# zp_zh.net
KiCad netlist of a schematic drawn in Altium Designer
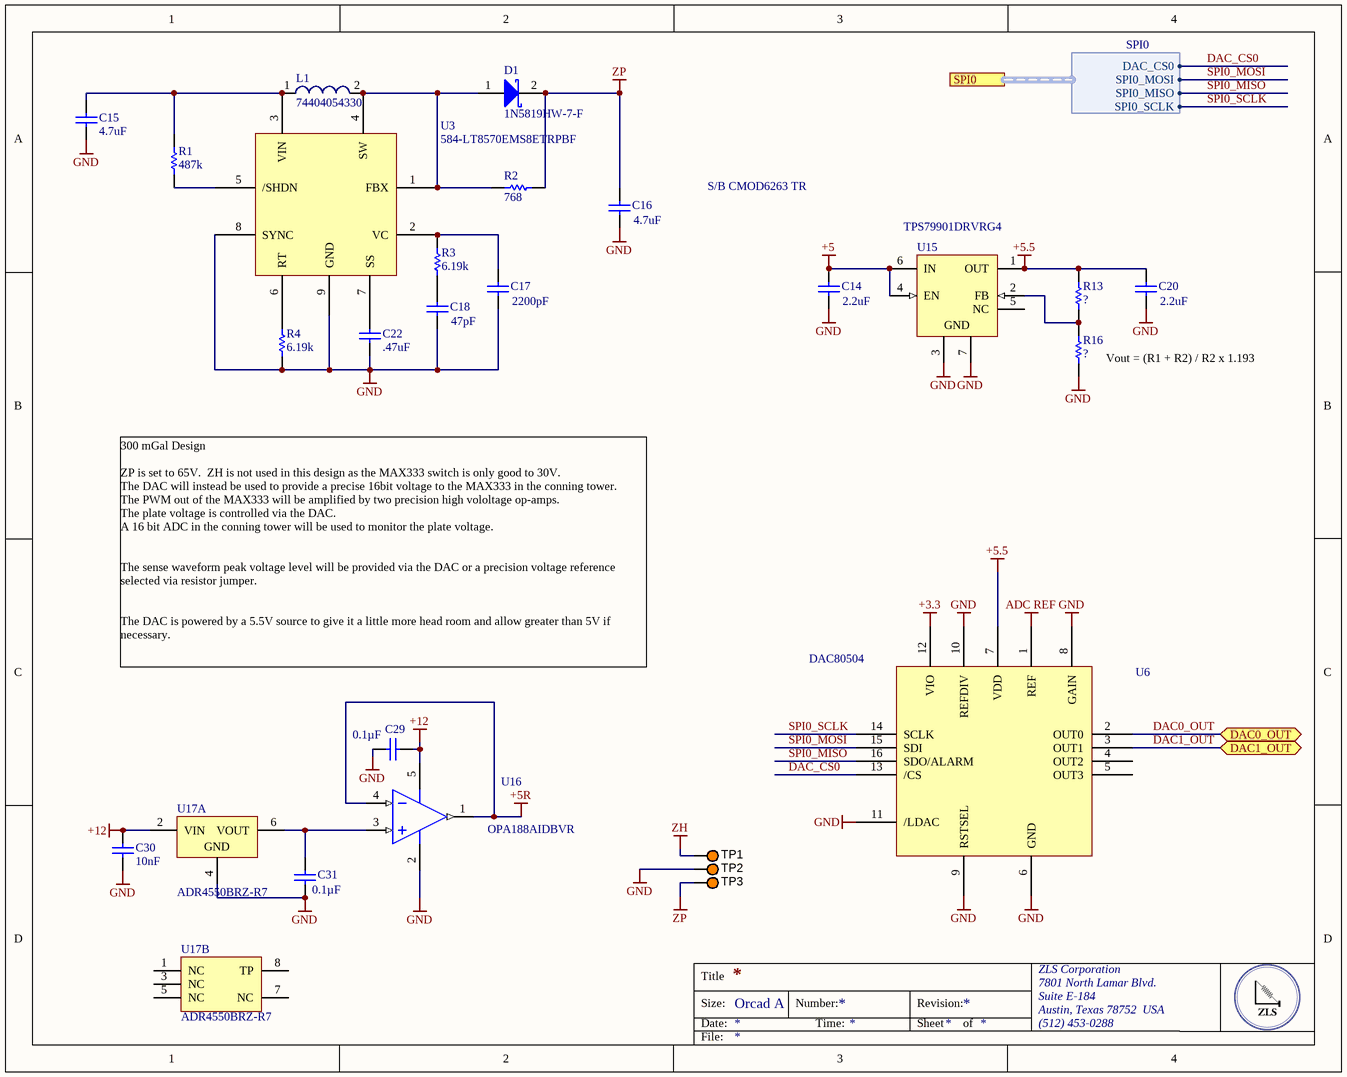
[diagram p0: zp_zh.SchDoc]

(export (version "E")
  (design (tool "Eeschema 10.0.6"))
  (components
    (comp (ref "C14")
      (value "CAP CER 1UF 25V X7R 0805")
      (footprint "CAPC0805(2012)155_L")
      (fields
        (field (name "MANUFACTURER") "Murata Electronics North America")
        (field (name "MANUFACTURER PART NUMBER") "GRM21BR71E105KA99L")
        (field (name "CAPACITANCE") "2.2uF")
        (field (name "TOLERANCE") "±10%")
      )
      (libsource (lib "Altium Content Vault") (part "CMP-1036-04882-1"))
    )
    (comp (ref "C15")
      (value "4.7uF")
      (footprint "CAPC0805(2012)155_L")
      (libsource (lib "Altium Content Vault") (part "CMP-1036-04882-1"))
    )
    (comp (ref "C16")
      (value "CAP CER 1UF 25V X7R 0805")
      (footprint "CAPC0805(2012)155_L")
      (fields
        (field (name "MANUFACTURER") "Murata Electronics North America")
        (field (name "MANUFACTURER PART NUMBER") "GRM21BR71E105KA99L")
        (field (name "CAPACITANCE") "4.7uF")
        (field (name "TOLERANCE") "±10%")
      )
      (libsource (lib "Altium Content Vault") (part "CMP-1036-04882-1"))
    )
    (comp (ref "C17")
      (value "CAP CER 1UF 25V X7R 0805")
      (footprint "CAPC0805(2012)155_L")
      (fields
        (field (name "MANUFACTURER") "Murata Electronics North America")
        (field (name "MANUFACTURER PART NUMBER") "GRM21BR71E105KA99L")
        (field (name "CAPACITANCE") "2200pF")
        (field (name "TOLERANCE") "±10%")
      )
      (libsource (lib "Altium Content Vault") (part "CMP-1036-04882-1"))
    )
    (comp (ref "C18")
      (value "CAP CER 1UF 25V X7R 0805")
      (footprint "CAPC0805(2012)155_L")
      (fields
        (field (name "MANUFACTURER") "Murata Electronics North America")
        (field (name "MANUFACTURER PART NUMBER") "GRM21BR71E105KA99L")
        (field (name "CAPACITANCE") "47pF")
        (field (name "TOLERANCE") "±10%")
      )
      (libsource (lib "Altium Content Vault") (part "CMP-1036-04882-1"))
    )
    (comp (ref "C20")
      (value "CAP CER 1UF 25V X7R 0805")
      (footprint "CAPC0805(2012)155_L")
      (fields
        (field (name "MANUFACTURER") "Murata Electronics North America")
        (field (name "MANUFACTURER PART NUMBER") "GRM21BR71E105KA99L")
        (field (name "CAPACITANCE") "2.2uF")
        (field (name "TOLERANCE") "±10%")
      )
      (libsource (lib "Altium Content Vault") (part "CMP-1036-04882-1"))
    )
    (comp (ref "C22")
      (value ".47uF")
      (footprint "CAPC0805(2012)155_L")
      (libsource (lib "Altium Content Vault") (part "CMP-1036-04882-1"))
    )
    (comp (ref "C29")
      (value "CAP CER 0.1UF 25V X7R 0805")
      (footprint "CAPC0805(2012)145_N")
      (fields
        (field (name "MANUFACTURER") "Murata Electronics North America")
        (field (name "MANUFACTURER PART NUMBER") "GRM21BR71E104KA01L")
        (field (name "CAPACITANCE") "0.1µF")
        (field (name "TOLERANCE") "±10%")
      )
      (libsource (lib "Altium Content Vault") (part "CMP-1036-04795-1"))
    )
    (comp (ref "C30")
      (value "Multilayer Ceramic Capacitors MLCC - SMD/SMT 0.01uF 50volts 10% X7R")
      (footprint "CAPC0805(2012)145_N")
      (fields
        (field (name "MANUFACTURER") "Kemet")
        (field (name "MANUFACTURER PART NUMBER") "C0805C103K5RACAUTO")
        (field (name "CAPACITANCE") "10nF")
        (field (name "TOLERANCE") "10%")
      )
      (libsource (lib "Altium Content Vault") (part "CMP-1036-04795-1"))
    )
    (comp (ref "C31")
      (value "CAP CER 0.1UF 25V X7R 0805")
      (footprint "CAPC0805(2012)145_N")
      (fields
        (field (name "MANUFACTURER") "Murata Electronics North America")
        (field (name "MANUFACTURER PART NUMBER") "GRM21BR71E104KA01L")
        (field (name "CAPACITANCE") "0.1µF")
        (field (name "TOLERANCE") "±10%")
      )
      (libsource (lib "Altium Content Vault") (part "CMP-1036-04795-1"))
    )
    (comp (ref "D1")
      (value "1N5819HW-7-F")
      (footprint "DIOD-SOD-123-2_V")
      (fields (field (name "MANUFACTURER") "Diodes Inc"))
      (libsource (lib "Altium Content Vault") (part "DIOD-DSKY-A1K2-2"))
    )
    (comp (ref "L1")
      (value "74404054330")
      (footprint "WE-LQS 5040")
      (description "WE-LQS SMD Power Inductor, L=33.0 µH")
      (fields (field (name "MANUFACTURER") "Wuerth Elektronik"))
      (libsource (lib "Altium Content Vault") (part "WE-IND-INDUCTOR-2"))
    )
    (comp (ref "R1")
      (value "487k")
      (footprint "RESC0805(2012)_L")
      (libsource (lib "Altium Content Vault") (part "CMP-1013-00215-1"))
    )
    (comp (ref "R2")
      (value "768")
      (footprint "RESC0805(2012)_L")
      (libsource (lib "Altium Content Vault") (part "CMP-1013-00215-1"))
    )
    (comp (ref "R3")
      (value "6.19k")
      (footprint "RESC0805(2012)_L")
      (libsource (lib "Altium Content Vault") (part "CMP-1013-00215-1"))
    )
    (comp (ref "R4")
      (value "6.19k")
      (footprint "RESC0805(2012)_L")
      (libsource (lib "Altium Content Vault") (part "CMP-1013-00215-1"))
    )
    (comp (ref "R13")
      (value "?")
      (footprint "RESC0805(2012)_L")
      (libsource (lib "Altium Content Vault") (part "CMP-1013-00215-1"))
    )
    (comp (ref "R16")
      (value "?")
      (footprint "RESC0805(2012)_L")
      (libsource (lib "Altium Content Vault") (part "CMP-1013-00215-1"))
    )
    (comp (ref "TP1")
      (value "5003")
      (footprint "KSTN-5003")
      (description "Test Point, Orange, 1-Pin THD, RoHS")
      (libsource (lib "Altium Content Vault") (part "CMP-1672-00009-1"))
    )
    (comp (ref "TP2")
      (value "5003")
      (footprint "KSTN-5003")
      (description "Test Point, Orange, 1-Pin THD, RoHS")
      (libsource (lib "Altium Content Vault") (part "CMP-1672-00009-1"))
    )
    (comp (ref "TP3")
      (value "5003")
      (footprint "KSTN-5003")
      (description "Test Point, Orange, 1-Pin THD, RoHS")
      (libsource (lib "Altium Content Vault") (part "CMP-1672-00009-1"))
    )
    (comp (ref "U3")
      (value "LT8570")
      (footprint "LT8570-MSOP")
      (description "IC REG MULT CONFIG INV ADJ 8MSOP")
      (fields (field (name "SUPPLIER PART NUMBER 1") "584-LT8570EMS8ETRPBF"))
      (libsource (lib "ZLS_Schematic_lib") (part "LT8570"))
    )
    (comp (ref "U6")
      (value "DAC80504")
      (footprint "DAC80504")
      (libsource (lib "ZLS_Schematic_lib") (part "DAC80504"))
    )
    (comp (ref "U15")
      (value "TPS79901DRVRG4")
      (footprint "TI-DRV6-1600X1000TP_V")
      (fields (field (name "MANUFACTURER") "Texas Instruments"))
      (libsource (lib "Altium Content Vault") (part "TI-TPS7XXXXDRV6-1600X1000TP"))
    )
    (comp (ref "U16")
      (value "OPA188AIDBVR")
      (footprint "DBV0005A_M")
      (fields (field (name "MANUFACTURER") "Texas Instruments"))
      (libsource (lib "Altium Content Vault") (part "CMP-0809-00005-2"))
    )
    (comp (ref "U17")
      (value "ADR4550BRZ-R7")
      (footprint "ADI-R-8_M")
      (fields (field (name "MANUFACTURER") "Analog Devices"))
      (libsource (lib "Altium Content Vault") (part "ADI-ADR45xx-R-8"))
    )
  )
  (nets
    (net (code "2") (name "+3.3") (class "Default")
      (node (ref "U6") (pin "12") (pinfunction "VIO_12") (pintype "passive"))
    )
    (net (code "3") (name "+5") (class "Default")
      (node (ref "C14") (pin "2") (pinfunction "2_2") (pintype "passive"))
      (node (ref "U15") (pin "4") (pinfunction "EN_4") (pintype "input"))
      (node (ref "U15") (pin "6") (pinfunction "IN_6") (pintype "power_in"))
    )
    (net (code "4") (name "+5.5") (class "Default")
      (node (ref "C20") (pin "2") (pinfunction "2_2") (pintype "passive"))
      (node (ref "R13") (pin "1") (pinfunction "1_1") (pintype "passive"))
      (node (ref "U15") (pin "1") (pinfunction "OUT_1") (pintype "power_in"))
      (node (ref "U6") (pin "7") (pinfunction "VDD_7") (pintype "passive"))
    )
    (net (code "5") (name "+5R") (class "Default")
      (node (ref "U16") (pin "1") (pinfunction "OUT_1") (pintype "output"))
      (node (ref "U16") (pin "4") (pinfunction "IN-_4") (pintype "input"))
    )
    (net (code "6") (name "+12") (class "Default")
      (node (ref "C29") (pin "2") (pinfunction "2_2") (pintype "passive"))
      (node (ref "C30") (pin "1") (pinfunction "1_1") (pintype "passive"))
      (node (ref "U16") (pin "5") (pinfunction "V+_5") (pintype "power_in"))
      (node (ref "U17") (pin "2") (pinfunction "VIN_2") (pintype "power_in"))
    )
    (net (code "7") (name "/DAC0_OUT") (class "Default")
      (node (ref "U6") (pin "2") (pinfunction "OUT0_2") (pintype "passive"))
    )
    (net (code "8") (name "/DAC1_OUT") (class "Default")
      (node (ref "U6") (pin "3") (pinfunction "OUT1_3") (pintype "passive"))
    )
    (net (code "9") (name "/DAC_CS0") (class "Default")
      (node (ref "U6") (pin "13") (pinfunction "/CS_13") (pintype "passive"))
    )
    (net (code "10") (name "/SPI0_MISO") (class "Default")
      (node (ref "U6") (pin "16") (pinfunction "SDO/ALARM_16") (pintype "passive"))
    )
    (net (code "11") (name "/SPI0_MOSI") (class "Default")
      (node (ref "U6") (pin "15") (pinfunction "SDI_15") (pintype "passive"))
    )
    (net (code "12") (name "/SPI0_SCLK") (class "Default")
      (node (ref "U6") (pin "14") (pinfunction "SCLK_14") (pintype "passive"))
    )
    (net (code "14") (name "ADC REF") (class "Default")
      (node (ref "U6") (pin "1") (pinfunction "REF_1") (pintype "passive"))
    )
    (net (code "15") (name "GND") (class "Default")
      (node (ref "C14") (pin "1") (pinfunction "1_1") (pintype "passive"))
      (node (ref "C15") (pin "1") (pinfunction "1_1") (pintype "passive"))
      (node (ref "C16") (pin "1") (pinfunction "1_1") (pintype "passive"))
      (node (ref "C17") (pin "1") (pinfunction "1_1") (pintype "passive"))
      (node (ref "C18") (pin "1") (pinfunction "1_1") (pintype "passive"))
      (node (ref "C20") (pin "1") (pinfunction "1_1") (pintype "passive"))
      (node (ref "C22") (pin "1") (pinfunction "1_1") (pintype "passive"))
      (node (ref "C29") (pin "1") (pinfunction "1_1") (pintype "passive"))
      (node (ref "C30") (pin "2") (pinfunction "2_2") (pintype "passive"))
      (node (ref "C31") (pin "2") (pinfunction "2_2") (pintype "passive"))
      (node (ref "R16") (pin "2") (pinfunction "2_2") (pintype "passive"))
      (node (ref "R4") (pin "2") (pinfunction "2_2") (pintype "passive"))
      (node (ref "TP2") (pin "1") (pinfunction "1_1") (pintype "passive"))
      (node (ref "U15") (pin "3") (pinfunction "GND_3") (pintype "power_in"))
      (node (ref "U15") (pin "7") (pinfunction "GND_7") (pintype "power_in"))
      (node (ref "U16") (pin "2") (pinfunction "V-_2") (pintype "power_in"))
      (node (ref "U17") (pin "4") (pinfunction "GND_4") (pintype "power_in"))
      (node (ref "U3") (pin "8") (pinfunction "SYNC_8") (pintype "passive"))
      (node (ref "U3") (pin "9") (pinfunction "GND_9") (pintype "passive"))
      (node (ref "U6") (pin "10") (pinfunction "REFDIV_10") (pintype "passive"))
      (node (ref "U6") (pin "11") (pinfunction "/LDAC_11") (pintype "passive"))
      (node (ref "U6") (pin "6") (pinfunction "GND_6") (pintype "passive"))
      (node (ref "U6") (pin "8") (pinfunction "GAIN_8") (pintype "passive"))
      (node (ref "U6") (pin "9") (pinfunction "RSTSEL_9") (pintype "passive"))
    )
    (net (code "16") (name "Net-(C18-Pad2)") (class "Default")
      (node (ref "C18") (pin "2") (pinfunction "2_2") (pintype "passive"))
      (node (ref "R3") (pin "2") (pinfunction "2_2") (pintype "passive"))
    )
    (net (code "17") (name "Net-(D1-A)") (class "Default")
      (node (ref "D1") (pin "1") (pinfunction "A_1") (pintype "passive"))
      (node (ref "L1") (pin "2") (pinfunction "2_2") (pintype "passive"))
      (node (ref "R2") (pin "2") (pinfunction "2_2") (pintype "passive"))
      (node (ref "U3") (pin "1") (pinfunction "FBX_1") (pintype "passive"))
      (node (ref "U3") (pin "4") (pinfunction "SW_4") (pintype "passive"))
    )
    (net (code "18") (name "Net-(U3-RT)") (class "Default")
      (node (ref "R4") (pin "1") (pinfunction "1_1") (pintype "passive"))
      (node (ref "U3") (pin "6") (pinfunction "RT_6") (pintype "passive"))
    )
    (net (code "19") (name "Net-(U3-SS)") (class "Default")
      (node (ref "C22") (pin "2") (pinfunction "2_2") (pintype "passive"))
      (node (ref "U3") (pin "7") (pinfunction "SS_7") (pintype "passive"))
    )
    (net (code "20") (name "Net-(U3-VC)") (class "Default")
      (node (ref "C17") (pin "2") (pinfunction "2_2") (pintype "passive"))
      (node (ref "R3") (pin "1") (pinfunction "1_1") (pintype "passive"))
      (node (ref "U3") (pin "2") (pinfunction "VC_2") (pintype "passive"))
    )
    (net (code "21") (name "Net-(U3-VIN)") (class "Default")
      (node (ref "C15") (pin "2") (pinfunction "2_2") (pintype "passive"))
      (node (ref "L1") (pin "1") (pinfunction "1_1") (pintype "passive"))
      (node (ref "R1") (pin "1") (pinfunction "1_1") (pintype "passive"))
      (node (ref "U3") (pin "3") (pinfunction "VIN_3") (pintype "passive"))
    )
    (net (code "22") (name "Net-(U3-{slash}SHDN)") (class "Default")
      (node (ref "R1") (pin "2") (pinfunction "2_2") (pintype "passive"))
      (node (ref "U3") (pin "5") (pinfunction "/SHDN_5") (pintype "passive"))
    )
    (net (code "23") (name "Net-(U15-FB)") (class "Default")
      (node (ref "R13") (pin "2") (pinfunction "2_2") (pintype "passive"))
      (node (ref "R16") (pin "1") (pinfunction "1_1") (pintype "passive"))
      (node (ref "U15") (pin "2") (pinfunction "FB_2") (pintype "input"))
    )
    (net (code "24") (name "Net-(U16-IN+)") (class "Default")
      (node (ref "C31") (pin "1") (pinfunction "1_1") (pintype "passive"))
      (node (ref "U16") (pin "3") (pinfunction "IN+_3") (pintype "input"))
      (node (ref "U17") (pin "6") (pinfunction "VOUT_6") (pintype "power_in"))
    )
    (net (code "25") (name "ZH") (class "Default")
      (node (ref "TP1") (pin "1") (pinfunction "1_1") (pintype "passive"))
    )
    (net (code "26") (name "ZP") (class "Default")
      (node (ref "C16") (pin "2") (pinfunction "2_2") (pintype "passive"))
      (node (ref "D1") (pin "2") (pinfunction "K_2") (pintype "passive"))
      (node (ref "R2") (pin "1") (pinfunction "1_1") (pintype "passive"))
      (node (ref "TP3") (pin "1") (pinfunction "1_1") (pintype "passive"))
    )
    (net (code "27") (name "unconnected-(U6-OUT2-Pad4)") (class "Default")
      (node (ref "U6") (pin "4") (pinfunction "OUT2_4") (pintype "passive"))
    )
    (net (code "28") (name "unconnected-(U6-OUT3-Pad5)") (class "Default")
      (node (ref "U6") (pin "5") (pinfunction "OUT3_5") (pintype "passive"))
    )
    (net (code "29") (name "unconnected-(U15-NC-Pad5)") (class "Default")
      (node (ref "U15") (pin "5") (pinfunction "NC_5") (pintype "passive"))
    )
    (net (code "30") (name "unconnected-(U17B-NC-Pad1)") (class "Default")
      (node (ref "U17") (pin "1") (pinfunction "NC_1") (pintype "passive"))
    )
    (net (code "31") (name "unconnected-(U17B-NC-Pad3)") (class "Default")
      (node (ref "U17") (pin "3") (pinfunction "NC_3") (pintype "passive"))
    )
    (net (code "32") (name "unconnected-(U17B-NC-Pad5)") (class "Default")
      (node (ref "U17") (pin "5") (pinfunction "NC_5") (pintype "passive"))
    )
    (net (code "33") (name "unconnected-(U17B-NC-Pad7)") (class "Default")
      (node (ref "U17") (pin "7") (pinfunction "NC_7") (pintype "passive"))
    )
    (net (code "34") (name "unconnected-(U17B-TP-Pad8)") (class "Default")
      (node (ref "U17") (pin "8") (pinfunction "TP_8") (pintype "passive"))
    )
  )
)
